# GREENLED.net
KiCad netlist of a schematic drawn in Altium Designer
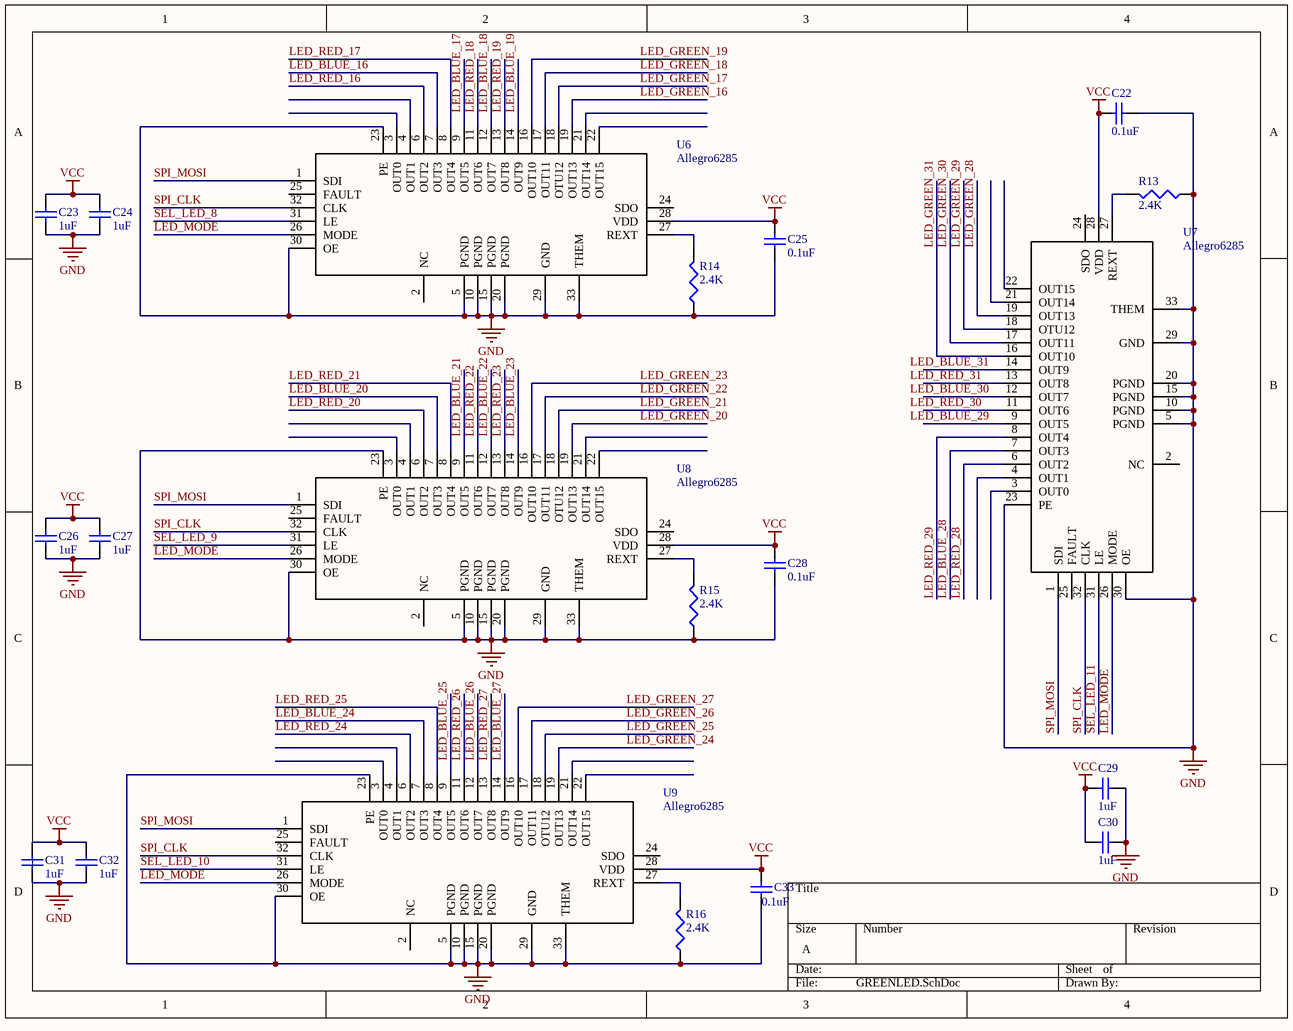
[diagram p0: GREENLED.SchDoc]

(export (version "E")
  (design (tool "Eeschema 10.0.6"))
  (components
    (comp (ref "C22")
      (value "0.1uF")
      (footprint "CAPC1005L")
      (description "Capacitor (Semiconductor SIM Model)")
      (fields (field (name "Comment") "Cap Semi") (field (name "PUBLISHER") "Altium Limited"))
      (libsource (lib "Miscellaneous Devices") (part "Cap Semi"))
    )
    (comp (ref "C23")
      (value "1uF")
      (footprint "CAPC1608L")
      (description "Capacitor (Semiconductor SIM Model)")
      (fields (field (name "Comment") "Cap Semi") (field (name "PUBLISHER") "Altium Limited"))
      (libsource (lib "Miscellaneous Devices") (part "Cap Semi"))
    )
    (comp (ref "C24")
      (value "1uF")
      (footprint "CAPC1608L")
      (description "Capacitor (Semiconductor SIM Model)")
      (fields (field (name "Comment") "Cap Semi") (field (name "PUBLISHER") "Altium Limited"))
      (libsource (lib "Miscellaneous Devices") (part "Cap Semi"))
    )
    (comp (ref "C25")
      (value "0.1uF")
      (footprint "CAPC1005L")
      (description "Capacitor (Semiconductor SIM Model)")
      (fields (field (name "Comment") "Cap Semi") (field (name "PUBLISHER") "Altium Limited"))
      (libsource (lib "Miscellaneous Devices") (part "Cap Semi"))
    )
    (comp (ref "C26")
      (value "1uF")
      (footprint "CAPC1608L")
      (description "Capacitor (Semiconductor SIM Model)")
      (fields (field (name "Comment") "Cap Semi") (field (name "PUBLISHER") "Altium Limited"))
      (libsource (lib "Miscellaneous Devices") (part "Cap Semi"))
    )
    (comp (ref "C27")
      (value "1uF")
      (footprint "CAPC1608L")
      (description "Capacitor (Semiconductor SIM Model)")
      (fields (field (name "Comment") "Cap Semi") (field (name "PUBLISHER") "Altium Limited"))
      (libsource (lib "Miscellaneous Devices") (part "Cap Semi"))
    )
    (comp (ref "C28")
      (value "0.1uF")
      (footprint "CAPC1005L")
      (description "Capacitor (Semiconductor SIM Model)")
      (fields (field (name "Comment") "Cap Semi") (field (name "PUBLISHER") "Altium Limited"))
      (libsource (lib "Miscellaneous Devices") (part "Cap Semi"))
    )
    (comp (ref "C29")
      (value "1uF")
      (footprint "CAPC1608L")
      (description "Capacitor (Semiconductor SIM Model)")
      (fields (field (name "Comment") "Cap Semi") (field (name "PUBLISHER") "Altium Limited"))
      (libsource (lib "Miscellaneous Devices") (part "Cap Semi"))
    )
    (comp (ref "C30")
      (value "1uF")
      (footprint "CAPC1608L")
      (description "Capacitor (Semiconductor SIM Model)")
      (fields (field (name "Comment") "Cap Semi") (field (name "PUBLISHER") "Altium Limited"))
      (libsource (lib "Miscellaneous Devices") (part "Cap Semi"))
    )
    (comp (ref "C31")
      (value "1uF")
      (footprint "CAPC1608L")
      (description "Capacitor (Semiconductor SIM Model)")
      (fields (field (name "Comment") "Cap Semi") (field (name "PUBLISHER") "Altium Limited"))
      (libsource (lib "Miscellaneous Devices") (part "Cap Semi"))
    )
    (comp (ref "C32")
      (value "1uF")
      (footprint "CAPC1608L")
      (description "Capacitor (Semiconductor SIM Model)")
      (fields (field (name "Comment") "Cap Semi") (field (name "PUBLISHER") "Altium Limited"))
      (libsource (lib "Miscellaneous Devices") (part "Cap Semi"))
    )
    (comp (ref "C33")
      (value "0.1uF")
      (footprint "CAPC1005L")
      (description "Capacitor (Semiconductor SIM Model)")
      (fields (field (name "Comment") "Cap Semi") (field (name "PUBLISHER") "Altium Limited"))
      (libsource (lib "Miscellaneous Devices") (part "Cap Semi"))
    )
    (comp (ref "R13")
      (value "2.4K")
      (footprint "RESC1608L")
      (description "Resistor")
      (fields (field (name "Comment") "Res3") (field (name "PUBLISHER") "Altium Limited"))
      (libsource (lib "Miscellaneous Devices") (part "Res3"))
    )
    (comp (ref "R14")
      (value "2.4K")
      (footprint "RESC1608L")
      (description "Resistor")
      (fields (field (name "Comment") "Res3") (field (name "PUBLISHER") "Altium Limited"))
      (libsource (lib "Miscellaneous Devices") (part "Res3"))
    )
    (comp (ref "R15")
      (value "2.4K")
      (footprint "RESC1608L")
      (description "Resistor")
      (fields (field (name "Comment") "Res3") (field (name "PUBLISHER") "Altium Limited"))
      (libsource (lib "Miscellaneous Devices") (part "Res3"))
    )
    (comp (ref "R16")
      (value "2.4K")
      (footprint "RESC1608L")
      (description "Resistor")
      (fields (field (name "Comment") "Res3") (field (name "PUBLISHER") "Altium Limited"))
      (libsource (lib "Miscellaneous Devices") (part "Res3"))
    )
    (comp (ref "U6")
      (value "Allegro6285")
      (footprint "QFN-32")
      (libsource (lib "mrone") (part "Allegro6285"))
    )
    (comp (ref "U7")
      (value "Allegro6285")
      (footprint "QFN-32")
      (libsource (lib "mrone") (part "Allegro6285"))
    )
    (comp (ref "U8")
      (value "Allegro6285")
      (footprint "QFN-32")
      (libsource (lib "mrone") (part "Allegro6285"))
    )
    (comp (ref "U9")
      (value "Allegro6285")
      (footprint "QFN-32")
      (libsource (lib "mrone") (part "Allegro6285"))
    )
  )
  (nets
    (net (code "1") (name "/LED_BLUE_16") (class "Default")
      (node (ref "U6") (pin "7") (pinfunction "OUT3_7") (pintype "passive"))
    )
    (net (code "2") (name "/LED_BLUE_17") (class "Default")
      (node (ref "U6") (pin "9") (pinfunction "OUT5_9") (pintype "passive"))
    )
    (net (code "3") (name "/LED_BLUE_18") (class "Default")
      (node (ref "U6") (pin "12") (pinfunction "OUT7_12") (pintype "passive"))
    )
    (net (code "4") (name "/LED_BLUE_19") (class "Default")
      (node (ref "U6") (pin "14") (pinfunction "OUT9_14") (pintype "passive"))
    )
    (net (code "5") (name "/LED_BLUE_20") (class "Default")
      (node (ref "U8") (pin "7") (pinfunction "OUT3_7") (pintype "passive"))
    )
    (net (code "6") (name "/LED_BLUE_21") (class "Default")
      (node (ref "U8") (pin "9") (pinfunction "OUT5_9") (pintype "passive"))
    )
    (net (code "7") (name "/LED_BLUE_22") (class "Default")
      (node (ref "U8") (pin "12") (pinfunction "OUT7_12") (pintype "passive"))
    )
    (net (code "8") (name "/LED_BLUE_23") (class "Default")
      (node (ref "U8") (pin "14") (pinfunction "OUT9_14") (pintype "passive"))
    )
    (net (code "9") (name "/LED_BLUE_24") (class "Default")
      (node (ref "U9") (pin "7") (pinfunction "OUT3_7") (pintype "passive"))
    )
    (net (code "10") (name "/LED_BLUE_25") (class "Default")
      (node (ref "U9") (pin "9") (pinfunction "OUT5_9") (pintype "passive"))
    )
    (net (code "11") (name "/LED_BLUE_26") (class "Default")
      (node (ref "U9") (pin "12") (pinfunction "OUT7_12") (pintype "passive"))
    )
    (net (code "12") (name "/LED_BLUE_27") (class "Default")
      (node (ref "U9") (pin "14") (pinfunction "OUT9_14") (pintype "passive"))
    )
    (net (code "13") (name "/LED_BLUE_28") (class "Default")
      (node (ref "U7") (pin "7") (pinfunction "OUT3_7") (pintype "passive"))
    )
    (net (code "17") (name "/LED_GREEN_16") (class "Default")
      (node (ref "U6") (pin "19") (pinfunction "OUT13_19") (pintype "passive"))
    )
    (net (code "18") (name "/LED_GREEN_17") (class "Default")
      (node (ref "U6") (pin "18") (pinfunction "OTU12_18") (pintype "passive"))
    )
    (net (code "19") (name "/LED_GREEN_18") (class "Default")
      (node (ref "U6") (pin "17") (pinfunction "OUT11_17") (pintype "passive"))
    )
    (net (code "20") (name "/LED_GREEN_19") (class "Default")
      (node (ref "U6") (pin "16") (pinfunction "OUT10_16") (pintype "passive"))
    )
    (net (code "21") (name "/LED_GREEN_20") (class "Default")
      (node (ref "U8") (pin "19") (pinfunction "OUT13_19") (pintype "passive"))
    )
    (net (code "22") (name "/LED_GREEN_21") (class "Default")
      (node (ref "U8") (pin "18") (pinfunction "OTU12_18") (pintype "passive"))
    )
    (net (code "23") (name "/LED_GREEN_22") (class "Default")
      (node (ref "U8") (pin "17") (pinfunction "OUT11_17") (pintype "passive"))
    )
    (net (code "24") (name "/LED_GREEN_23") (class "Default")
      (node (ref "U8") (pin "16") (pinfunction "OUT10_16") (pintype "passive"))
    )
    (net (code "25") (name "/LED_GREEN_24") (class "Default")
      (node (ref "U9") (pin "19") (pinfunction "OUT13_19") (pintype "passive"))
    )
    (net (code "26") (name "/LED_GREEN_25") (class "Default")
      (node (ref "U9") (pin "18") (pinfunction "OTU12_18") (pintype "passive"))
    )
    (net (code "27") (name "/LED_GREEN_26") (class "Default")
      (node (ref "U9") (pin "17") (pinfunction "OUT11_17") (pintype "passive"))
    )
    (net (code "28") (name "/LED_GREEN_27") (class "Default")
      (node (ref "U9") (pin "16") (pinfunction "OUT10_16") (pintype "passive"))
    )
    (net (code "29") (name "/LED_GREEN_28") (class "Default")
      (node (ref "U7") (pin "19") (pinfunction "OUT13_19") (pintype "passive"))
    )
    (net (code "30") (name "/LED_GREEN_29") (class "Default")
      (node (ref "U7") (pin "18") (pinfunction "OTU12_18") (pintype "passive"))
    )
    (net (code "31") (name "/LED_GREEN_30") (class "Default")
      (node (ref "U7") (pin "17") (pinfunction "OUT11_17") (pintype "passive"))
    )
    (net (code "32") (name "/LED_GREEN_31") (class "Default")
      (node (ref "U7") (pin "16") (pinfunction "OUT10_16") (pintype "passive"))
    )
    (net (code "33") (name "/LED_MODE") (class "Default")
      (node (ref "U6") (pin "26") (pinfunction "MODE_26") (pintype "passive"))
      (node (ref "U7") (pin "26") (pinfunction "MODE_26") (pintype "passive"))
      (node (ref "U8") (pin "26") (pinfunction "MODE_26") (pintype "passive"))
      (node (ref "U9") (pin "26") (pinfunction "MODE_26") (pintype "passive"))
    )
    (net (code "34") (name "/LED_RED_16") (class "Default")
      (node (ref "U6") (pin "6") (pinfunction "OUT2_6") (pintype "passive"))
    )
    (net (code "35") (name "/LED_RED_17") (class "Default")
      (node (ref "U6") (pin "8") (pinfunction "OUT4_8") (pintype "passive"))
    )
    (net (code "36") (name "/LED_RED_18") (class "Default")
      (node (ref "U6") (pin "11") (pinfunction "OUT6_11") (pintype "passive"))
    )
    (net (code "37") (name "/LED_RED_19") (class "Default")
      (node (ref "U6") (pin "13") (pinfunction "OUT8_13") (pintype "passive"))
    )
    (net (code "38") (name "/LED_RED_20") (class "Default")
      (node (ref "U8") (pin "6") (pinfunction "OUT2_6") (pintype "passive"))
    )
    (net (code "39") (name "/LED_RED_21") (class "Default")
      (node (ref "U8") (pin "8") (pinfunction "OUT4_8") (pintype "passive"))
    )
    (net (code "40") (name "/LED_RED_22") (class "Default")
      (node (ref "U8") (pin "11") (pinfunction "OUT6_11") (pintype "passive"))
    )
    (net (code "41") (name "/LED_RED_23") (class "Default")
      (node (ref "U8") (pin "13") (pinfunction "OUT8_13") (pintype "passive"))
    )
    (net (code "42") (name "/LED_RED_24") (class "Default")
      (node (ref "U9") (pin "6") (pinfunction "OUT2_6") (pintype "passive"))
    )
    (net (code "43") (name "/LED_RED_25") (class "Default")
      (node (ref "U9") (pin "8") (pinfunction "OUT4_8") (pintype "passive"))
    )
    (net (code "44") (name "/LED_RED_26") (class "Default")
      (node (ref "U9") (pin "11") (pinfunction "OUT6_11") (pintype "passive"))
    )
    (net (code "45") (name "/LED_RED_27") (class "Default")
      (node (ref "U9") (pin "13") (pinfunction "OUT8_13") (pintype "passive"))
    )
    (net (code "46") (name "/LED_RED_28") (class "Default")
      (node (ref "U7") (pin "6") (pinfunction "OUT2_6") (pintype "passive"))
    )
    (net (code "47") (name "/LED_RED_29") (class "Default")
      (node (ref "U7") (pin "8") (pinfunction "OUT4_8") (pintype "passive"))
    )
    (net (code "50") (name "/SEL_LED_8") (class "Default")
      (node (ref "U6") (pin "31") (pinfunction "LE_31") (pintype "passive"))
    )
    (net (code "51") (name "/SEL_LED_9") (class "Default")
      (node (ref "U8") (pin "31") (pinfunction "LE_31") (pintype "passive"))
    )
    (net (code "52") (name "/SEL_LED_10") (class "Default")
      (node (ref "U9") (pin "31") (pinfunction "LE_31") (pintype "passive"))
    )
    (net (code "53") (name "/SEL_LED_11") (class "Default")
      (node (ref "U7") (pin "31") (pinfunction "LE_31") (pintype "passive"))
    )
    (net (code "54") (name "/SPI_CLK") (class "Default")
      (node (ref "U6") (pin "32") (pinfunction "CLK_32") (pintype "passive"))
      (node (ref "U7") (pin "32") (pinfunction "CLK_32") (pintype "passive"))
      (node (ref "U8") (pin "32") (pinfunction "CLK_32") (pintype "passive"))
      (node (ref "U9") (pin "32") (pinfunction "CLK_32") (pintype "passive"))
    )
    (net (code "55") (name "/SPI_MOSI") (class "Default")
      (node (ref "U6") (pin "1") (pinfunction "SDI_1") (pintype "passive"))
      (node (ref "U7") (pin "1") (pinfunction "SDI_1") (pintype "passive"))
      (node (ref "U8") (pin "1") (pinfunction "SDI_1") (pintype "passive"))
      (node (ref "U9") (pin "1") (pinfunction "SDI_1") (pintype "passive"))
    )
    (net (code "56") (name "GND") (class "Default")
      (node (ref "C22") (pin "1") (pinfunction "1_1") (pintype "passive"))
      (node (ref "C23") (pin "1") (pinfunction "1_1") (pintype "passive"))
      (node (ref "C24") (pin "1") (pinfunction "1_1") (pintype "passive"))
      (node (ref "C25") (pin "1") (pinfunction "1_1") (pintype "passive"))
      (node (ref "C26") (pin "1") (pinfunction "1_1") (pintype "passive"))
      (node (ref "C27") (pin "1") (pinfunction "1_1") (pintype "passive"))
      (node (ref "C28") (pin "1") (pinfunction "1_1") (pintype "passive"))
      (node (ref "C29") (pin "1") (pinfunction "1_1") (pintype "passive"))
      (node (ref "C30") (pin "1") (pinfunction "1_1") (pintype "passive"))
      (node (ref "C31") (pin "1") (pinfunction "1_1") (pintype "passive"))
      (node (ref "C32") (pin "1") (pinfunction "1_1") (pintype "passive"))
      (node (ref "C33") (pin "1") (pinfunction "1_1") (pintype "passive"))
      (node (ref "R13") (pin "1") (pinfunction "1_1") (pintype "passive"))
      (node (ref "R14") (pin "1") (pinfunction "1_1") (pintype "passive"))
      (node (ref "R15") (pin "1") (pinfunction "1_1") (pintype "passive"))
      (node (ref "R16") (pin "1") (pinfunction "1_1") (pintype "passive"))
      (node (ref "U6") (pin "10") (pinfunction "PGND_10") (pintype "passive"))
      (node (ref "U6") (pin "15") (pinfunction "PGND_15") (pintype "passive"))
      (node (ref "U6") (pin "20") (pinfunction "PGND_20") (pintype "passive"))
      (node (ref "U6") (pin "23") (pinfunction "PE_23") (pintype "passive"))
      (node (ref "U6") (pin "29") (pinfunction "GND_29") (pintype "passive"))
      (node (ref "U6") (pin "30") (pinfunction "OE_30") (pintype "passive"))
      (node (ref "U6") (pin "33") (pinfunction "THEM_33") (pintype "passive"))
      (node (ref "U6") (pin "5") (pinfunction "PGND_5") (pintype "passive"))
      (node (ref "U7") (pin "10") (pinfunction "PGND_10") (pintype "passive"))
      (node (ref "U7") (pin "15") (pinfunction "PGND_15") (pintype "passive"))
      (node (ref "U7") (pin "20") (pinfunction "PGND_20") (pintype "passive"))
      (node (ref "U7") (pin "23") (pinfunction "PE_23") (pintype "passive"))
      (node (ref "U7") (pin "29") (pinfunction "GND_29") (pintype "passive"))
      (node (ref "U7") (pin "30") (pinfunction "OE_30") (pintype "passive"))
      (node (ref "U7") (pin "33") (pinfunction "THEM_33") (pintype "passive"))
      (node (ref "U7") (pin "5") (pinfunction "PGND_5") (pintype "passive"))
      (node (ref "U8") (pin "10") (pinfunction "PGND_10") (pintype "passive"))
      (node (ref "U8") (pin "15") (pinfunction "PGND_15") (pintype "passive"))
      (node (ref "U8") (pin "20") (pinfunction "PGND_20") (pintype "passive"))
      (node (ref "U8") (pin "23") (pinfunction "PE_23") (pintype "passive"))
      (node (ref "U8") (pin "29") (pinfunction "GND_29") (pintype "passive"))
      (node (ref "U8") (pin "30") (pinfunction "OE_30") (pintype "passive"))
      (node (ref "U8") (pin "33") (pinfunction "THEM_33") (pintype "passive"))
      (node (ref "U8") (pin "5") (pinfunction "PGND_5") (pintype "passive"))
      (node (ref "U9") (pin "10") (pinfunction "PGND_10") (pintype "passive"))
      (node (ref "U9") (pin "15") (pinfunction "PGND_15") (pintype "passive"))
      (node (ref "U9") (pin "20") (pinfunction "PGND_20") (pintype "passive"))
      (node (ref "U9") (pin "23") (pinfunction "PE_23") (pintype "passive"))
      (node (ref "U9") (pin "29") (pinfunction "GND_29") (pintype "passive"))
      (node (ref "U9") (pin "30") (pinfunction "OE_30") (pintype "passive"))
      (node (ref "U9") (pin "33") (pinfunction "THEM_33") (pintype "passive"))
      (node (ref "U9") (pin "5") (pinfunction "PGND_5") (pintype "passive"))
    )
    (net (code "57") (name "Net-(U6-REXT)") (class "Default")
      (node (ref "R14") (pin "2") (pinfunction "2_2") (pintype "passive"))
      (node (ref "U6") (pin "27") (pinfunction "REXT_27") (pintype "passive"))
    )
    (net (code "58") (name "Net-(U7-REXT)") (class "Default")
      (node (ref "R13") (pin "2") (pinfunction "2_2") (pintype "passive"))
      (node (ref "U7") (pin "27") (pinfunction "REXT_27") (pintype "passive"))
    )
    (net (code "59") (name "Net-(U8-REXT)") (class "Default")
      (node (ref "R15") (pin "2") (pinfunction "2_2") (pintype "passive"))
      (node (ref "U8") (pin "27") (pinfunction "REXT_27") (pintype "passive"))
    )
    (net (code "60") (name "Net-(U9-REXT)") (class "Default")
      (node (ref "R16") (pin "2") (pinfunction "2_2") (pintype "passive"))
      (node (ref "U9") (pin "27") (pinfunction "REXT_27") (pintype "passive"))
    )
    (net (code "61") (name "VCC") (class "Default")
      (node (ref "C22") (pin "2") (pinfunction "2_2") (pintype "passive"))
      (node (ref "C23") (pin "2") (pinfunction "2_2") (pintype "passive"))
      (node (ref "C24") (pin "2") (pinfunction "2_2") (pintype "passive"))
      (node (ref "C25") (pin "2") (pinfunction "2_2") (pintype "passive"))
      (node (ref "C26") (pin "2") (pinfunction "2_2") (pintype "passive"))
      (node (ref "C27") (pin "2") (pinfunction "2_2") (pintype "passive"))
      (node (ref "C28") (pin "2") (pinfunction "2_2") (pintype "passive"))
      (node (ref "C29") (pin "2") (pinfunction "2_2") (pintype "passive"))
      (node (ref "C30") (pin "2") (pinfunction "2_2") (pintype "passive"))
      (node (ref "C31") (pin "2") (pinfunction "2_2") (pintype "passive"))
      (node (ref "C32") (pin "2") (pinfunction "2_2") (pintype "passive"))
      (node (ref "C33") (pin "2") (pinfunction "2_2") (pintype "passive"))
      (node (ref "U6") (pin "28") (pinfunction "VDD_28") (pintype "passive"))
      (node (ref "U7") (pin "28") (pinfunction "VDD_28") (pintype "passive"))
      (node (ref "U8") (pin "28") (pinfunction "VDD_28") (pintype "passive"))
      (node (ref "U9") (pin "28") (pinfunction "VDD_28") (pintype "passive"))
    )
    (net (code "62") (name "unconnected-(U6-FAULT-Pad25)") (class "Default")
      (node (ref "U6") (pin "25") (pinfunction "FAULT_25") (pintype "passive"))
    )
    (net (code "63") (name "unconnected-(U6-NC-Pad2)") (class "Default")
      (node (ref "U6") (pin "2") (pinfunction "NC_2") (pintype "passive"))
    )
    (net (code "64") (name "unconnected-(U6-OUT0-Pad3)") (class "Default")
      (node (ref "U6") (pin "3") (pinfunction "OUT0_3") (pintype "passive"))
    )
    (net (code "65") (name "unconnected-(U6-OUT1-Pad4)") (class "Default")
      (node (ref "U6") (pin "4") (pinfunction "OUT1_4") (pintype "passive"))
    )
    (net (code "66") (name "unconnected-(U6-OUT14-Pad21)") (class "Default")
      (node (ref "U6") (pin "21") (pinfunction "OUT14_21") (pintype "passive"))
    )
    (net (code "67") (name "unconnected-(U6-OUT15-Pad22)") (class "Default")
      (node (ref "U6") (pin "22") (pinfunction "OUT15_22") (pintype "passive"))
    )
    (net (code "68") (name "unconnected-(U6-SDO-Pad24)") (class "Default")
      (node (ref "U6") (pin "24") (pinfunction "SDO_24") (pintype "passive"))
    )
    (net (code "69") (name "unconnected-(U7-FAULT-Pad25)") (class "Default")
      (node (ref "U7") (pin "25") (pinfunction "FAULT_25") (pintype "passive"))
    )
    (net (code "70") (name "unconnected-(U7-NC-Pad2)") (class "Default")
      (node (ref "U7") (pin "2") (pinfunction "NC_2") (pintype "passive"))
    )
    (net (code "71") (name "unconnected-(U7-OUT0-Pad3)") (class "Default")
      (node (ref "U7") (pin "3") (pinfunction "OUT0_3") (pintype "passive"))
    )
    (net (code "72") (name "unconnected-(U7-OUT1-Pad4)") (class "Default")
      (node (ref "U7") (pin "4") (pinfunction "OUT1_4") (pintype "passive"))
    )
    (net (code "73") (name "unconnected-(U7-OUT5-Pad9)") (class "Default")
      (node (ref "U7") (pin "9") (pinfunction "OUT5_9") (pintype "passive"))
    )
    (net (code "74") (name "unconnected-(U7-OUT6-Pad11)") (class "Default")
      (node (ref "U7") (pin "11") (pinfunction "OUT6_11") (pintype "passive"))
    )
    (net (code "75") (name "unconnected-(U7-OUT7-Pad12)") (class "Default")
      (node (ref "U7") (pin "12") (pinfunction "OUT7_12") (pintype "passive"))
    )
    (net (code "76") (name "unconnected-(U7-OUT8-Pad13)") (class "Default")
      (node (ref "U7") (pin "13") (pinfunction "OUT8_13") (pintype "passive"))
    )
    (net (code "77") (name "unconnected-(U7-OUT9-Pad14)") (class "Default")
      (node (ref "U7") (pin "14") (pinfunction "OUT9_14") (pintype "passive"))
    )
    (net (code "78") (name "unconnected-(U7-OUT14-Pad21)") (class "Default")
      (node (ref "U7") (pin "21") (pinfunction "OUT14_21") (pintype "passive"))
    )
    (net (code "79") (name "unconnected-(U7-OUT15-Pad22)") (class "Default")
      (node (ref "U7") (pin "22") (pinfunction "OUT15_22") (pintype "passive"))
    )
    (net (code "80") (name "unconnected-(U7-SDO-Pad24)") (class "Default")
      (node (ref "U7") (pin "24") (pinfunction "SDO_24") (pintype "passive"))
    )
    (net (code "81") (name "unconnected-(U8-FAULT-Pad25)") (class "Default")
      (node (ref "U8") (pin "25") (pinfunction "FAULT_25") (pintype "passive"))
    )
    (net (code "82") (name "unconnected-(U8-NC-Pad2)") (class "Default")
      (node (ref "U8") (pin "2") (pinfunction "NC_2") (pintype "passive"))
    )
    (net (code "83") (name "unconnected-(U8-OUT0-Pad3)") (class "Default")
      (node (ref "U8") (pin "3") (pinfunction "OUT0_3") (pintype "passive"))
    )
    (net (code "84") (name "unconnected-(U8-OUT1-Pad4)") (class "Default")
      (node (ref "U8") (pin "4") (pinfunction "OUT1_4") (pintype "passive"))
    )
    (net (code "85") (name "unconnected-(U8-OUT14-Pad21)") (class "Default")
      (node (ref "U8") (pin "21") (pinfunction "OUT14_21") (pintype "passive"))
    )
    (net (code "86") (name "unconnected-(U8-OUT15-Pad22)") (class "Default")
      (node (ref "U8") (pin "22") (pinfunction "OUT15_22") (pintype "passive"))
    )
    (net (code "87") (name "unconnected-(U8-SDO-Pad24)") (class "Default")
      (node (ref "U8") (pin "24") (pinfunction "SDO_24") (pintype "passive"))
    )
    (net (code "88") (name "unconnected-(U9-FAULT-Pad25)") (class "Default")
      (node (ref "U9") (pin "25") (pinfunction "FAULT_25") (pintype "passive"))
    )
    (net (code "89") (name "unconnected-(U9-NC-Pad2)") (class "Default")
      (node (ref "U9") (pin "2") (pinfunction "NC_2") (pintype "passive"))
    )
    (net (code "90") (name "unconnected-(U9-OUT0-Pad3)") (class "Default")
      (node (ref "U9") (pin "3") (pinfunction "OUT0_3") (pintype "passive"))
    )
    (net (code "91") (name "unconnected-(U9-OUT1-Pad4)") (class "Default")
      (node (ref "U9") (pin "4") (pinfunction "OUT1_4") (pintype "passive"))
    )
    (net (code "92") (name "unconnected-(U9-OUT14-Pad21)") (class "Default")
      (node (ref "U9") (pin "21") (pinfunction "OUT14_21") (pintype "passive"))
    )
    (net (code "93") (name "unconnected-(U9-OUT15-Pad22)") (class "Default")
      (node (ref "U9") (pin "22") (pinfunction "OUT15_22") (pintype "passive"))
    )
    (net (code "94") (name "unconnected-(U9-SDO-Pad24)") (class "Default")
      (node (ref "U9") (pin "24") (pinfunction "SDO_24") (pintype "passive"))
    )
  )
)
